# Line_3_3V.net
KiCad netlist of a schematic drawn in Altium Designer
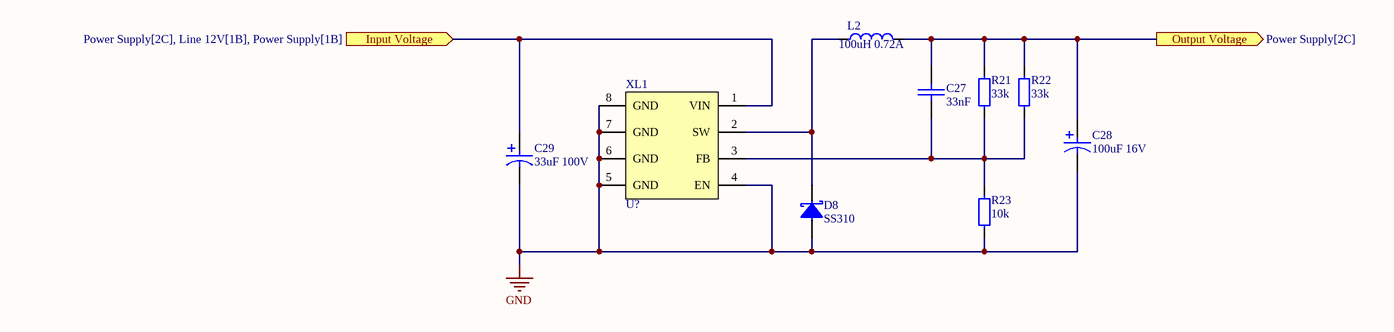
[diagram p0: Line 3.3V.SchDoc]

(export (version "E")
  (design (tool "Eeschema 10.0.6"))
  (components
    (comp (ref "C27")
      (value "33nF")
      (footprint "0805 Capicator")
      (description "0805 C0G 3.3нФ 50В 5%")
      (fields
        (field (name "PART NUMBER") "GRM21BR72A333KA01L")
        (field (name "MANUFACTURER") "Murata Manufacturing")
      )
      (libsource (lib "BRT_Components") (part "Cap 33nF (0805) 50V"))
    )
    (comp (ref "C28")
      (value "100uF 16V")
      (footprint "BAR CAP 6.3x5.4")
      (description "100uF 16V 6.3Х5.4mm")
      (libsource (lib "Altium_Library") (part "Capacitor 100uF 16V"))
    )
    (comp (ref "C29")
      (value "33uF 100V")
      (footprint "Bar Cap 10x10.2")
      (description "EEEFK2A330P, 33uF 100V ±20% (10 X 10.2mm)")
      (libsource (lib "Altium_Library") (part "Capacitor 33uF 100V (10x10.2mm)"))
    )
    (comp (ref "D8")
      (value "SS310")
      (footprint "DIODE: SMB")
      (description "100B 3.0A Schottky diode")
      (libsource (lib "Altium_Library") (part "Schottky diode SS310"))
    )
    (comp (ref "L2")
      (value "100uH 0.72A")
      (footprint "CD75")
      (description "CD75-101K 100uH 0.72A")
      (libsource (lib "Altium_Library") (part "Inductor 100uH 0.72A"))
    )
    (comp (ref "R21")
      (value "33k")
      (footprint "RES: 0805")
      (description "33kOhm 0805 0.125W 5%")
      (libsource (lib "Altium_Library") (part "Resistor 33k (0805)"))
    )
    (comp (ref "R22")
      (value "33k")
      (footprint "RES: 0805")
      (description "33kOhm 0805 0.125W 5%")
      (libsource (lib "Altium_Library") (part "Resistor 33k (0805)"))
    )
    (comp (ref "R23")
      (value "10k")
      (footprint "0805 Resistor")
      (description "0.125W 0805 10k, 1%")
      (fields (field (name "PART NUMBER") "RC0805FR-0710KL") (field (name "MANUFACTURER") "Taiwan"))
      (libsource (lib "BRT_Components") (part "Res 10k (0805)"))
    )
    (comp (ref "XL1")
      (value "U?")
      (footprint "HSOP-8")
      (description "0.4A 150KHz 80V Buck DC to DC Converter")
      (libsource (lib "Altium_Library") (part "DC/DC Buck XL7005A"))
    )
  )
  (nets
    (net (code "1") (name "/Input Voltage") (class "Default")
      (node (ref "C29") (pin "2") (pinfunction "2_2") (pintype "passive"))
      (node (ref "XL1") (pin "1") (pinfunction "VIN_1") (pintype "passive"))
    )
    (net (code "2") (name "/Output Voltage") (class "Default")
      (node (ref "C27") (pin "2") (pintype "passive"))
      (node (ref "C28") (pin "2") (pinfunction "2_2") (pintype "passive"))
      (node (ref "L2") (pin "2") (pinfunction "2_2") (pintype "passive"))
      (node (ref "R21") (pin "2") (pinfunction "2_2") (pintype "passive"))
      (node (ref "R22") (pin "2") (pinfunction "2_2") (pintype "passive"))
    )
    (net (code "3") (name "GND") (class "Default")
      (node (ref "C28") (pin "1") (pinfunction "1_1") (pintype "passive"))
      (node (ref "C29") (pin "1") (pinfunction "1_1") (pintype "passive"))
      (node (ref "D8") (pin "1") (pinfunction "1_1") (pintype "passive"))
      (node (ref "R23") (pin "1") (pinfunction "1_1") (pintype "passive"))
      (node (ref "XL1") (pin "4") (pinfunction "EN_4") (pintype "passive"))
      (node (ref "XL1") (pin "5") (pinfunction "GND_5") (pintype "power_in"))
      (node (ref "XL1") (pin "6") (pinfunction "GND_6") (pintype "power_in"))
      (node (ref "XL1") (pin "7") (pinfunction "GND_7") (pintype "power_in"))
      (node (ref "XL1") (pin "8") (pinfunction "GND_8") (pintype "power_in"))
    )
    (net (code "4") (name "Net-(XL1-FB)") (class "Default")
      (node (ref "C27") (pin "1") (pintype "passive"))
      (node (ref "R21") (pin "1") (pinfunction "1_1") (pintype "passive"))
      (node (ref "R22") (pin "1") (pinfunction "1_1") (pintype "passive"))
      (node (ref "R23") (pin "2") (pinfunction "2_2") (pintype "passive"))
      (node (ref "XL1") (pin "3") (pinfunction "FB_3") (pintype "passive"))
    )
    (net (code "5") (name "Net-(XL1-SW)") (class "Default")
      (node (ref "D8") (pin "2") (pinfunction "2_2") (pintype "passive"))
      (node (ref "L2") (pin "1") (pinfunction "1_1") (pintype "passive"))
      (node (ref "XL1") (pin "2") (pinfunction "SW_2") (pintype "passive"))
    )
  )
)
